# use0_1.net
KiCad netlist of a schematic drawn in EasyEDA Pro
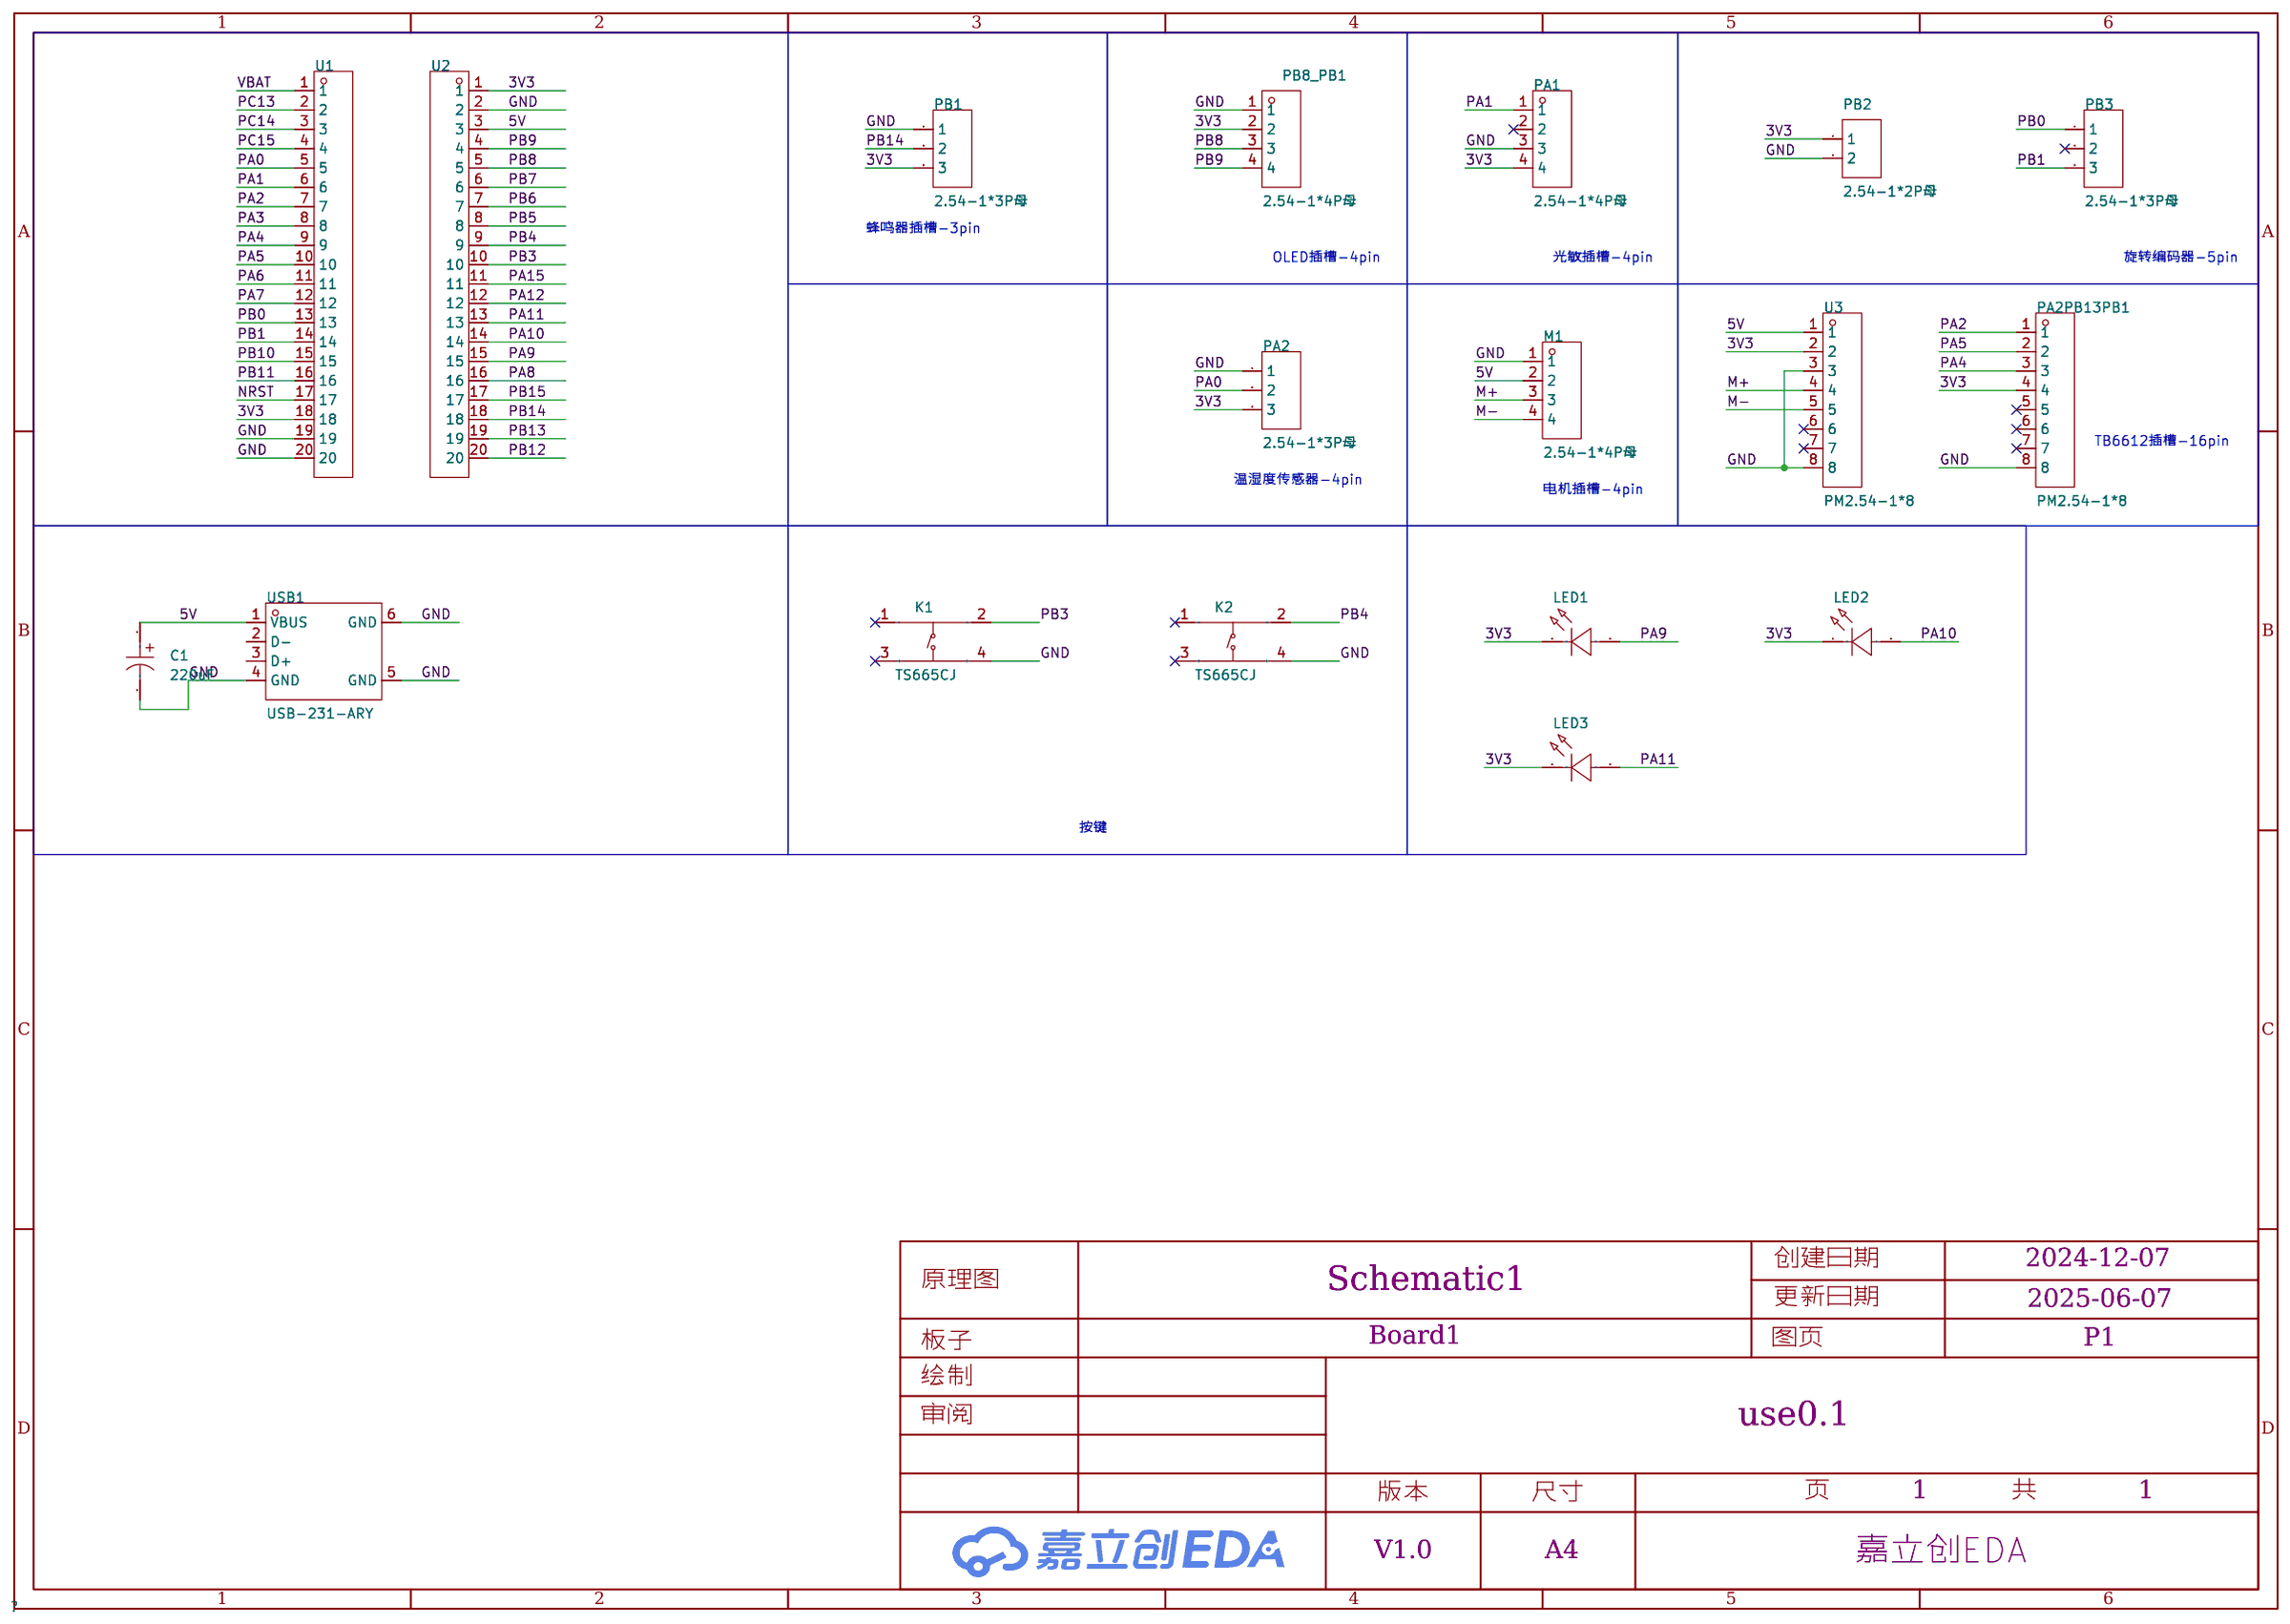
[diagram p0: schematic sheet]

(export (version "E")
  (design (tool "Eeschema 10.0.6"))
  (components
    (comp (ref "C1")
      (value "220uF")
      (footprint "easyedapro:CAP-TH_BD5.0-P2.00-D0.5-FD")
      (description "容值:220uF;精度:±20%;额定电压:10V;纹波电流:170mA@120Hz;")
      (fields (field (name "Manufacturer Part") "ERA10V220M5X11") (field (name "Manufacturer") "JIERR(捷而瑞)"))
      (libsource (lib "easyedapro") (part "ERA10V220M5X11"))
    )
    (comp (ref "K1")
      (value "TS665CJ")
      (footprint "easyedapro:SW-TH_4P-L6.0-W6.0-P4.50-LS6.5")
      (description "电路结构:单刀单掷;按钮形状:圆形按钮;安装方式:直插;开关长度:6mm;开关宽度:6mm;开关高度:5mm;触点电流:50mA;额定电压(DC):12V;带灯:-;机械寿命:-;")
      (fields (field (name "Manufacturer") "SHOU HAN(首韩)"))
      (libsource (lib "easyedapro") (part "TS665CJ"))
    )
    (comp (ref "K2")
      (value "TS665CJ")
      (footprint "easyedapro:SW-TH_4P-L6.0-W6.0-P4.50-LS6.5")
      (description "电路结构:单刀单掷;按钮形状:圆形按钮;安装方式:直插;开关长度:6mm;开关宽度:6mm;开关高度:5mm;触点电流:50mA;额定电压(DC):12V;带灯:-;机械寿命:-;")
      (fields (field (name "Manufacturer") "SHOU HAN(首韩)"))
      (libsource (lib "easyedapro") (part "TS665CJ"))
    )
    (comp (ref "LED1")
      (value "NFD5408BC")
      (footprint "easyedapro:LED-TH_BD5.7-P2.54-RD")
      (description "发光颜色:蓝色;功率:200mW;主波长:460nm~470nm;发光角度:20°;工作温度:-30°C~+85°C;")
      (fields (field (name "Manufacturer") "国星光电"))
      (libsource (lib "easyedapro") (part "NFD5408BC"))
    )
    (comp (ref "LED2")
      (value "NFD5408BC")
      (footprint "easyedapro:LED-TH_BD5.7-P2.54-RD")
      (description "发光颜色:蓝色;功率:200mW;主波长:460nm~470nm;发光角度:20°;工作温度:-30°C~+85°C;")
      (fields (field (name "Manufacturer") "国星光电"))
      (libsource (lib "easyedapro") (part "NFD5408BC"))
    )
    (comp (ref "LED3")
      (value "NFD5408BC")
      (footprint "easyedapro:LED-TH_BD5.7-P2.54-RD")
      (description "发光颜色:蓝色;功率:200mW;主波长:460nm~470nm;发光角度:20°;工作温度:-30°C~+85°C;")
      (fields (field (name "Manufacturer") "国星光电"))
      (libsource (lib "easyedapro") (part "NFD5408BC"))
    )
    (comp (ref "M1")
      (value "2.54-1*4P母")
      (footprint "easyedapro:HDR-TH_4P-P2.54-V-F")
      (fields (field (name "Manufacturer") "BOOMELE(博穆精密)"))
      (libsource (lib "easyedapro") (part "2.54-1*4P母"))
    )
    (comp (ref "PA1")
      (value "2.54-1*4P母")
      (footprint "easyedapro:HDR-TH_4P-P2.54-V-F")
      (fields (field (name "Manufacturer") "BOOMELE(博穆精密)"))
      (libsource (lib "easyedapro") (part "2.54-1*4P母"))
    )
    (comp (ref "PA2")
      (value "2.54-1*3P母")
      (footprint "easyedapro:HDR-TH_3P-P2.54-V-F")
      (description "间距:2.54mm;行距:-;安装类型:直插;排数:单排;总孔位数:3P;塑高:-;触头材质:-;触头镀层:金;")
      (fields (field (name "Manufacturer") "BOOMELE(博穆精密)"))
      (libsource (lib "easyedapro") (part "Header-Female-2.54_1x3"))
    )
    (comp (ref "PA2PB13PB1")
      (value "PM2.54-1*8")
      (footprint "easyedapro:HDR-TH_8P-P2.54-V-F")
      (fields (field (name "Manufacturer") "ZHOURI(洲日)"))
      (libsource (lib "easyedapro") (part "PM2.54-1*8"))
    )
    (comp (ref "PB1")
      (value "2.54-1*3P母")
      (footprint "easyedapro:HDR-TH_3P-P2.54-V-F")
      (description "间距:2.54mm;行距:-;安装类型:直插;排数:单排;总孔位数:3P;塑高:-;触头材质:-;触头镀层:金;")
      (fields (field (name "Manufacturer") "BOOMELE(博穆精密)"))
      (libsource (lib "easyedapro") (part "Header-Female-2.54_1x3"))
    )
    (comp (ref "PB2")
      (value "2.54-1*2P母")
      (footprint "easyedapro:HDR-TH_2P-P2.54-V-F")
      (description "插孔结构:1x2P;间距:2.54mm;行距:-;安装类型:直插;排数:单排;总孔位数:2P;塑高:-;触头材质:-;触头镀层:-;")
      (fields (field (name "Manufacturer") "BOOMELE(博穆精密)"))
      (libsource (lib "easyedapro") (part "Header-Female-2.54_1x2"))
    )
    (comp (ref "PB3")
      (value "2.54-1*3P母")
      (footprint "easyedapro:HDR-TH_3P-P2.54-V-F")
      (description "间距:2.54mm;行距:-;安装类型:直插;排数:单排;总孔位数:3P;塑高:-;触头材质:-;触头镀层:金;")
      (fields (field (name "Manufacturer") "BOOMELE(博穆精密)"))
      (libsource (lib "easyedapro") (part "Header-Female-2.54_1x3"))
    )
    (comp (ref "PB8_PB1")
      (value "2.54-1*4P母")
      (footprint "easyedapro:HDR-TH_4P-P2.54-V-F")
      (fields (field (name "Manufacturer") "BOOMELE(博穆精密)"))
      (libsource (lib "easyedapro") (part "2.54-1*4P母"))
    )
    (comp (ref "U1")
      (value "KH-2.54FH-1X20P-H8.5")
      (footprint "easyedapro:HDR-TH_20P-P2.54-V-F-2")
      (fields (field (name "Manufacturer") "kinghelm(金航标)"))
      (libsource (lib "easyedapro") (part "KH-2.54FH-1X20P-H8.5"))
    )
    (comp (ref "U2")
      (value "KH-2.54FH-1X20P-H8.5")
      (footprint "easyedapro:HDR-TH_20P-P2.54-V-F-2")
      (fields (field (name "Manufacturer") "kinghelm(金航标)"))
      (libsource (lib "easyedapro") (part "KH-2.54FH-1X20P-H8.5"))
    )
    (comp (ref "U3")
      (value "PM2.54-1*8")
      (footprint "easyedapro:HDR-TH_8P-P2.54-V-F")
      (fields (field (name "Manufacturer") "ZHOURI(洲日)"))
      (libsource (lib "easyedapro") (part "PM2.54-1*8"))
    )
    (comp (ref "USB1")
      (value "USB-231-ARY")
      (footprint "easyedapro:USB-A-TH_USB-231-ARY")
      (fields (field (name "Manufacturer") "XUNPU(讯普)"))
      (libsource (lib "easyedapro") (part "USB-231-ARY"))
    )
  )
  (nets
    (net (code "1") (name "/3V3") (class "Default")
      (node (ref "LED1") (pin "1") (pinfunction "K_1") (pintype "unspecified"))
      (node (ref "LED2") (pin "1") (pinfunction "K_1") (pintype "unspecified"))
      (node (ref "LED3") (pin "1") (pinfunction "K_1") (pintype "unspecified"))
      (node (ref "PA1") (pin "4") (pinfunction "4_4") (pintype "unspecified"))
      (node (ref "PA2") (pin "3") (pinfunction "3_3") (pintype "input"))
      (node (ref "PA2PB13PB1") (pin "4") (pinfunction "4_4") (pintype "unspecified"))
      (node (ref "PB1") (pin "3") (pinfunction "3_3") (pintype "input"))
      (node (ref "PB2") (pin "1") (pinfunction "1_1") (pintype "input"))
      (node (ref "PB8_PB1") (pin "2") (pinfunction "2_2") (pintype "unspecified"))
      (node (ref "U1") (pin "18") (pinfunction "18_18") (pintype "unspecified"))
      (node (ref "U2") (pin "1") (pinfunction "1_1") (pintype "unspecified"))
      (node (ref "U3") (pin "2") (pinfunction "2_2") (pintype "unspecified"))
    )
    (net (code "2") (name "/5V") (class "Default")
      (node (ref "C1") (pin "1") (pinfunction "1_1") (pintype "input"))
      (node (ref "M1") (pin "2") (pinfunction "2_2") (pintype "unspecified"))
      (node (ref "U2") (pin "3") (pinfunction "3_3") (pintype "unspecified"))
      (node (ref "U3") (pin "1") (pinfunction "1_1") (pintype "unspecified"))
      (node (ref "USB1") (pin "1") (pinfunction "VBUS_1") (pintype "unspecified"))
    )
    (net (code "3") (name "/GND") (class "Default")
      (node (ref "C1") (pin "2") (pinfunction "2_2") (pintype "input"))
      (node (ref "K1") (pin "4") (pinfunction "D_4") (pintype "unspecified"))
      (node (ref "K2") (pin "4") (pinfunction "D_4") (pintype "unspecified"))
      (node (ref "M1") (pin "1") (pinfunction "1_1") (pintype "unspecified"))
      (node (ref "PA1") (pin "3") (pinfunction "3_3") (pintype "unspecified"))
      (node (ref "PA2") (pin "1") (pinfunction "1_1") (pintype "input"))
      (node (ref "PA2PB13PB1") (pin "8") (pinfunction "8_8") (pintype "unspecified"))
      (node (ref "PB1") (pin "1") (pinfunction "1_1") (pintype "input"))
      (node (ref "PB2") (pin "2") (pinfunction "2_2") (pintype "input"))
      (node (ref "PB8_PB1") (pin "1") (pinfunction "1_1") (pintype "unspecified"))
      (node (ref "U1") (pin "19") (pinfunction "19_19") (pintype "unspecified"))
      (node (ref "U1") (pin "20") (pinfunction "20_20") (pintype "unspecified"))
      (node (ref "U2") (pin "2") (pinfunction "2_2") (pintype "unspecified"))
      (node (ref "U3") (pin "3") (pinfunction "3_3") (pintype "unspecified"))
      (node (ref "U3") (pin "8") (pinfunction "8_8") (pintype "unspecified"))
      (node (ref "USB1") (pin "4") (pinfunction "GND_4") (pintype "unspecified"))
      (node (ref "USB1") (pin "5") (pinfunction "GND_5") (pintype "unspecified"))
      (node (ref "USB1") (pin "6") (pinfunction "GND_6") (pintype "unspecified"))
    )
    (net (code "4") (name "/M+") (class "Default")
      (node (ref "M1") (pin "3") (pinfunction "3_3") (pintype "unspecified"))
      (node (ref "U3") (pin "4") (pinfunction "4_4") (pintype "unspecified"))
    )
    (net (code "5") (name "/M-") (class "Default")
      (node (ref "M1") (pin "4") (pinfunction "4_4") (pintype "unspecified"))
      (node (ref "U3") (pin "5") (pinfunction "5_5") (pintype "unspecified"))
    )
    (net (code "6") (name "/NRST") (class "Default")
      (node (ref "U1") (pin "17") (pinfunction "17_17") (pintype "unspecified"))
    )
    (net (code "7") (name "/PA0") (class "Default")
      (node (ref "PA2") (pin "2") (pinfunction "2_2") (pintype "input"))
      (node (ref "U1") (pin "5") (pinfunction "5_5") (pintype "unspecified"))
    )
    (net (code "8") (name "/PA1") (class "Default")
      (node (ref "PA1") (pin "1") (pinfunction "1_1") (pintype "unspecified"))
      (node (ref "U1") (pin "6") (pinfunction "6_6") (pintype "unspecified"))
    )
    (net (code "9") (name "/PA2") (class "Default")
      (node (ref "PA2PB13PB1") (pin "1") (pinfunction "1_1") (pintype "unspecified"))
      (node (ref "U1") (pin "7") (pinfunction "7_7") (pintype "unspecified"))
    )
    (net (code "10") (name "/PA3") (class "Default")
      (node (ref "U1") (pin "8") (pinfunction "8_8") (pintype "unspecified"))
    )
    (net (code "11") (name "/PA4") (class "Default")
      (node (ref "PA2PB13PB1") (pin "3") (pinfunction "3_3") (pintype "unspecified"))
      (node (ref "U1") (pin "9") (pinfunction "9_9") (pintype "unspecified"))
    )
    (net (code "12") (name "/PA5") (class "Default")
      (node (ref "PA2PB13PB1") (pin "2") (pinfunction "2_2") (pintype "unspecified"))
      (node (ref "U1") (pin "10") (pinfunction "10_10") (pintype "unspecified"))
    )
    (net (code "13") (name "/PA6") (class "Default")
      (node (ref "U1") (pin "11") (pinfunction "11_11") (pintype "unspecified"))
    )
    (net (code "14") (name "/PA7") (class "Default")
      (node (ref "U1") (pin "12") (pinfunction "12_12") (pintype "unspecified"))
    )
    (net (code "15") (name "/PA8") (class "Default")
      (node (ref "U2") (pin "16") (pinfunction "16_16") (pintype "unspecified"))
    )
    (net (code "16") (name "/PA9") (class "Default")
      (node (ref "LED1") (pin "2") (pinfunction "A_2") (pintype "unspecified"))
      (node (ref "U2") (pin "15") (pinfunction "15_15") (pintype "unspecified"))
    )
    (net (code "17") (name "/PA10") (class "Default")
      (node (ref "LED2") (pin "2") (pinfunction "A_2") (pintype "unspecified"))
      (node (ref "U2") (pin "14") (pinfunction "14_14") (pintype "unspecified"))
    )
    (net (code "18") (name "/PA11") (class "Default")
      (node (ref "LED3") (pin "2") (pinfunction "A_2") (pintype "unspecified"))
      (node (ref "U2") (pin "13") (pinfunction "13_13") (pintype "unspecified"))
    )
    (net (code "19") (name "/PA12") (class "Default")
      (node (ref "U2") (pin "12") (pinfunction "12_12") (pintype "unspecified"))
    )
    (net (code "20") (name "/PA15") (class "Default")
      (node (ref "U2") (pin "11") (pinfunction "11_11") (pintype "unspecified"))
    )
    (net (code "21") (name "/PB0") (class "Default")
      (node (ref "PB3") (pin "1") (pinfunction "1_1") (pintype "input"))
      (node (ref "U1") (pin "13") (pinfunction "13_13") (pintype "unspecified"))
    )
    (net (code "22") (name "/PB1") (class "Default")
      (node (ref "PB3") (pin "3") (pinfunction "3_3") (pintype "input"))
      (node (ref "U1") (pin "14") (pinfunction "14_14") (pintype "unspecified"))
    )
    (net (code "23") (name "/PB3") (class "Default")
      (node (ref "K1") (pin "2") (pinfunction "B_2") (pintype "unspecified"))
      (node (ref "U2") (pin "10") (pinfunction "10_10") (pintype "unspecified"))
    )
    (net (code "24") (name "/PB4") (class "Default")
      (node (ref "K2") (pin "2") (pinfunction "B_2") (pintype "unspecified"))
      (node (ref "U2") (pin "9") (pinfunction "9_9") (pintype "unspecified"))
    )
    (net (code "25") (name "/PB5") (class "Default")
      (node (ref "U2") (pin "8") (pinfunction "8_8") (pintype "unspecified"))
    )
    (net (code "26") (name "/PB6") (class "Default")
      (node (ref "U2") (pin "7") (pinfunction "7_7") (pintype "unspecified"))
    )
    (net (code "27") (name "/PB7") (class "Default")
      (node (ref "U2") (pin "6") (pinfunction "6_6") (pintype "unspecified"))
    )
    (net (code "28") (name "/PB8") (class "Default")
      (node (ref "PB8_PB1") (pin "3") (pinfunction "3_3") (pintype "unspecified"))
      (node (ref "U2") (pin "5") (pinfunction "5_5") (pintype "unspecified"))
    )
    (net (code "29") (name "/PB9") (class "Default")
      (node (ref "PB8_PB1") (pin "4") (pinfunction "4_4") (pintype "unspecified"))
      (node (ref "U2") (pin "4") (pinfunction "4_4") (pintype "unspecified"))
    )
    (net (code "30") (name "/PB10") (class "Default")
      (node (ref "U1") (pin "15") (pinfunction "15_15") (pintype "unspecified"))
    )
    (net (code "31") (name "/PB11") (class "Default")
      (node (ref "U1") (pin "16") (pinfunction "16_16") (pintype "unspecified"))
    )
    (net (code "32") (name "/PB12") (class "Default")
      (node (ref "U2") (pin "20") (pinfunction "20_20") (pintype "unspecified"))
    )
    (net (code "33") (name "/PB13") (class "Default")
      (node (ref "U2") (pin "19") (pinfunction "19_19") (pintype "unspecified"))
    )
    (net (code "34") (name "/PB14") (class "Default")
      (node (ref "PB1") (pin "2") (pinfunction "2_2") (pintype "input"))
      (node (ref "U2") (pin "18") (pinfunction "18_18") (pintype "unspecified"))
    )
    (net (code "35") (name "/PB15") (class "Default")
      (node (ref "U2") (pin "17") (pinfunction "17_17") (pintype "unspecified"))
    )
    (net (code "36") (name "/PC13") (class "Default")
      (node (ref "U1") (pin "2") (pinfunction "2_2") (pintype "unspecified"))
    )
    (net (code "37") (name "/PC14") (class "Default")
      (node (ref "U1") (pin "3") (pinfunction "3_3") (pintype "unspecified"))
    )
    (net (code "38") (name "/PC15") (class "Default")
      (node (ref "U1") (pin "4") (pinfunction "4_4") (pintype "unspecified"))
    )
    (net (code "39") (name "/VBAT") (class "Default")
      (node (ref "U1") (pin "1") (pinfunction "1_1") (pintype "unspecified"))
    )
    (net (code "40") (name "unconnected-(K1-A-Pad1)") (class "Default")
      (node (ref "K1") (pin "1") (pinfunction "A_1") (pintype "unspecified+no_connect"))
    )
    (net (code "41") (name "unconnected-(K1-C-Pad3)") (class "Default")
      (node (ref "K1") (pin "3") (pinfunction "C_3") (pintype "unspecified+no_connect"))
    )
    (net (code "42") (name "unconnected-(K2-A-Pad1)") (class "Default")
      (node (ref "K2") (pin "1") (pinfunction "A_1") (pintype "unspecified+no_connect"))
    )
    (net (code "43") (name "unconnected-(K2-C-Pad3)") (class "Default")
      (node (ref "K2") (pin "3") (pinfunction "C_3") (pintype "unspecified+no_connect"))
    )
    (net (code "44") (name "unconnected-(PA1-Pad2)") (class "Default")
      (node (ref "PA1") (pin "2") (pinfunction "2_2") (pintype "unspecified+no_connect"))
    )
    (net (code "45") (name "unconnected-(PA2PB13PB1-Pad5)") (class "Default")
      (node (ref "PA2PB13PB1") (pin "5") (pinfunction "5_5") (pintype "unspecified+no_connect"))
    )
    (net (code "46") (name "unconnected-(PA2PB13PB1-Pad6)") (class "Default")
      (node (ref "PA2PB13PB1") (pin "6") (pinfunction "6_6") (pintype "unspecified+no_connect"))
    )
    (net (code "47") (name "unconnected-(PA2PB13PB1-Pad7)") (class "Default")
      (node (ref "PA2PB13PB1") (pin "7") (pinfunction "7_7") (pintype "unspecified+no_connect"))
    )
    (net (code "48") (name "unconnected-(PB3-Pad2)") (class "Default")
      (node (ref "PB3") (pin "2") (pinfunction "2_2") (pintype "input+no_connect"))
    )
    (net (code "49") (name "unconnected-(U3-Pad6)") (class "Default")
      (node (ref "U3") (pin "6") (pinfunction "6_6") (pintype "unspecified+no_connect"))
    )
    (net (code "50") (name "unconnected-(U3-Pad7)") (class "Default")
      (node (ref "U3") (pin "7") (pinfunction "7_7") (pintype "unspecified+no_connect"))
    )
    (net (code "51") (name "unconnected-(USB1-D+-Pad3)") (class "Default")
      (node (ref "USB1") (pin "3") (pinfunction "D+_3") (pintype "unspecified"))
    )
    (net (code "52") (name "unconnected-(USB1-D--Pad2)") (class "Default")
      (node (ref "USB1") (pin "2") (pinfunction "D-_2") (pintype "unspecified"))
    )
  )
)
